# electric_imp_breakout.net
KiCad netlist of a schematic drawn in EAGLE
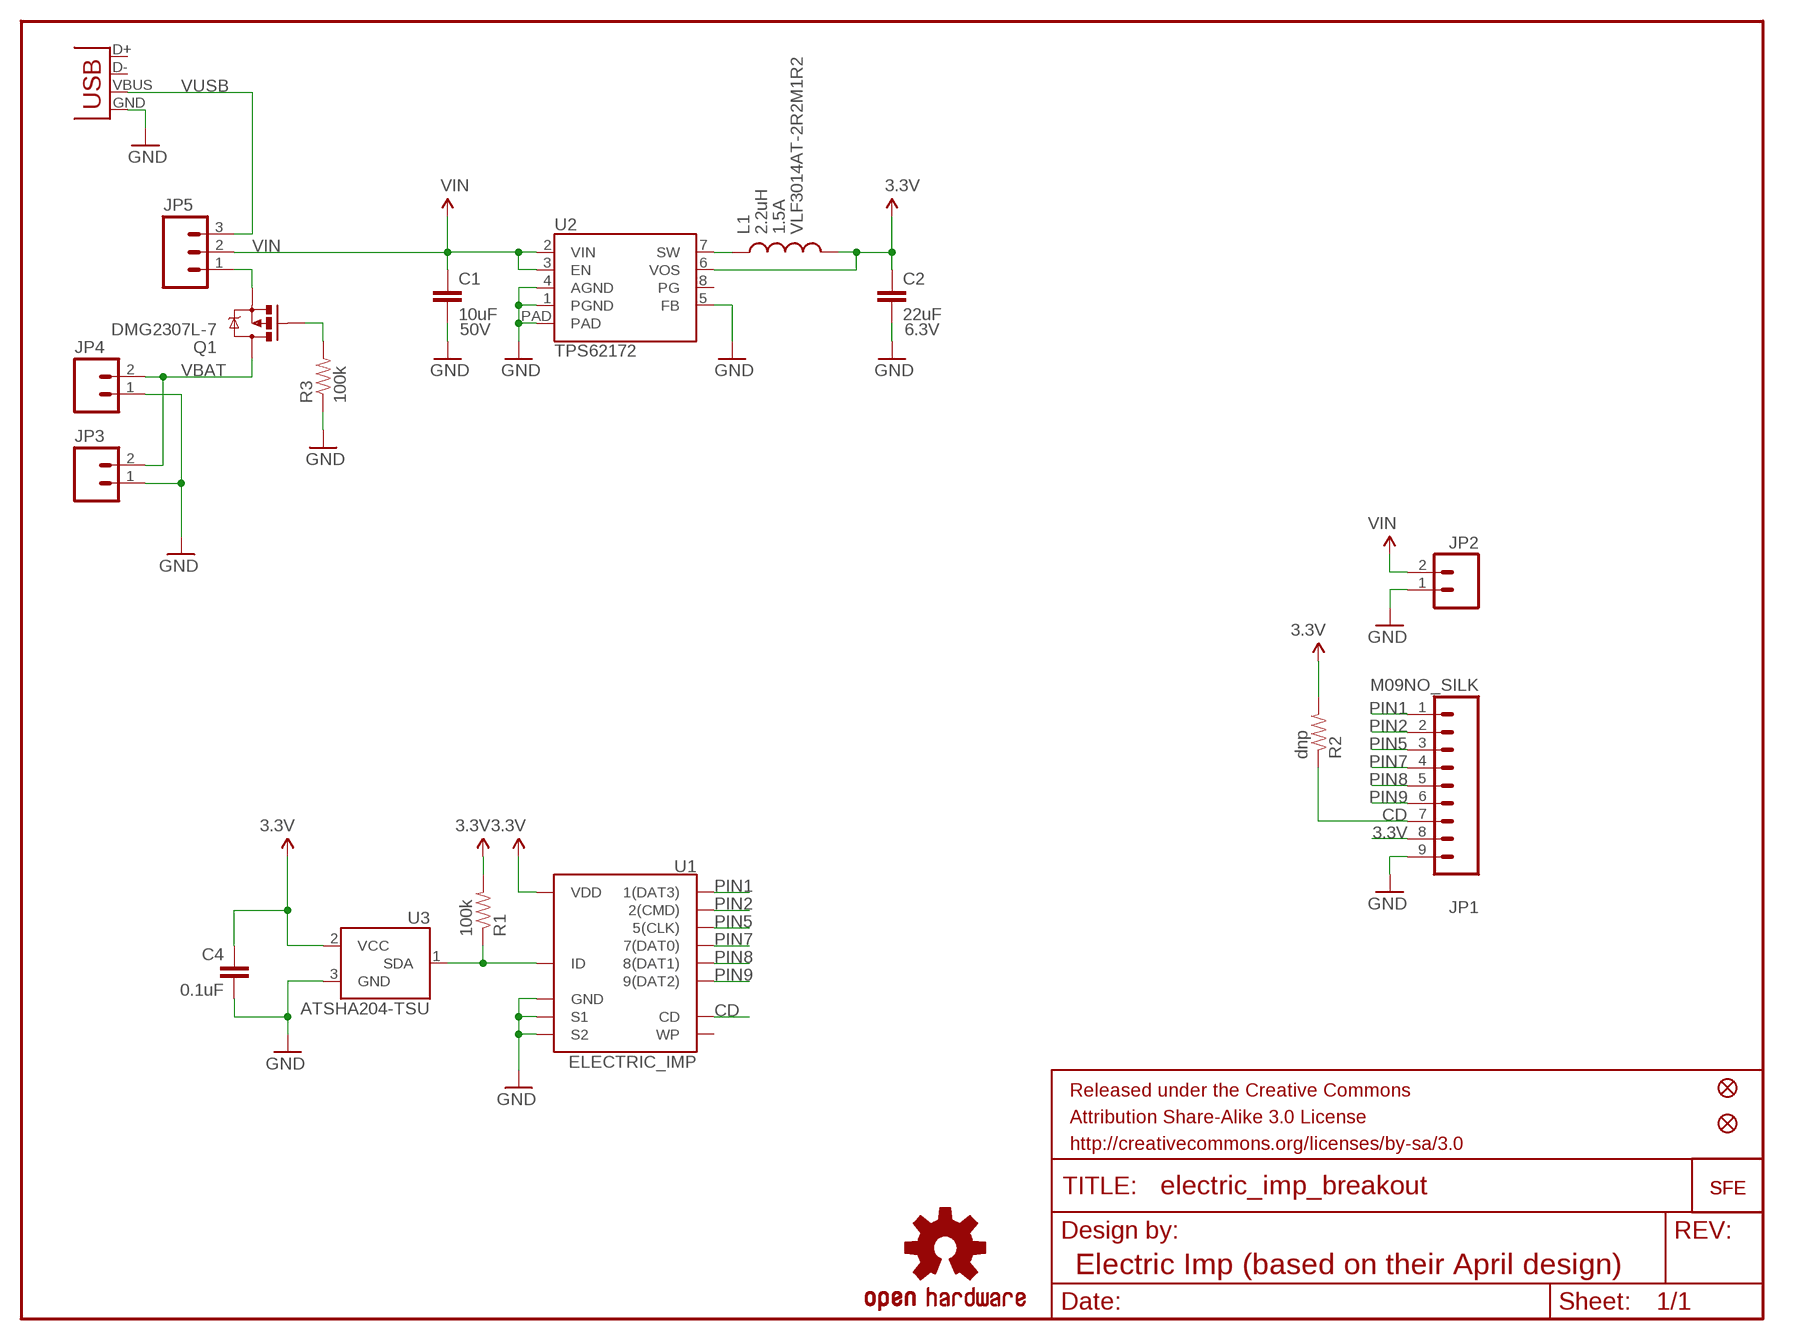
[diagram p0: schematic, sheet 1]

(export (version "E")
  (design (tool "Eeschema 10.0.6"))
  (components
    (comp (ref "C1")
      (value "10uF")
      (footprint "eagle-import:1210")
      (libsource (lib "eagle-import") (part "CAP1210"))
    )
    (comp (ref "C2")
      (value "22uF")
      (footprint "eagle-import:0805")
      (libsource (lib "eagle-import") (part "CAP0805"))
    )
    (comp (ref "C4")
      (value "0.1uF")
      (footprint "eagle-import:0402-CAP")
      (libsource (lib "eagle-import") (part "CAP0402-CAP"))
    )
    (comp (ref "JP1")
      (value "M09NO_SILK")
      (footprint "eagle-import:1X09_NO_SILK")
      (libsource (lib "eagle-import") (part "M09NO_SILK"))
    )
    (comp (ref "JP2")
      (value "M021X02_NO_SILK")
      (footprint "eagle-import:1X02_NO_SILK")
      (libsource (lib "eagle-import") (part "M021X02_NO_SILK"))
    )
    (comp (ref "JP3")
      (value "M02SMD")
      (footprint "eagle-import:1X02_SMD")
      (libsource (lib "eagle-import") (part "M02SMD"))
    )
    (comp (ref "JP4")
      (value "M02-JST-2-PTH-NO_SILK")
      (footprint "eagle-import:JST-2-PTH-NS")
      (libsource (lib "eagle-import") (part "M02-JST-2-PTH-NO_SILK"))
    )
    (comp (ref "JP5")
      (value "M031X03_NO_SILK")
      (footprint "eagle-import:1X03_NO_SILK")
      (libsource (lib "eagle-import") (part "M031X03_NO_SILK"))
    )
    (comp (ref "JP6")
      (value "LOGO-SFESK")
      (footprint "eagle-import:SFE-LOGO-FLAME")
      (libsource (lib "eagle-import") (part "LOGO-SFESK"))
    )
    (comp (ref "JP7")
      (value "LOGO-SFENEW")
      (footprint "eagle-import:SFE-NEW-WEBLOGO")
      (libsource (lib "eagle-import") (part "LOGO-SFENEW"))
    )
    (comp (ref "JP8")
      (value "FIDUCIALUFIDUCIAL")
      (footprint "eagle-import:MICRO-FIDUCIAL")
      (libsource (lib "eagle-import") (part "FIDUCIALUFIDUCIAL"))
    )
    (comp (ref "JP9")
      (value "FIDUCIALUFIDUCIAL")
      (footprint "eagle-import:MICRO-FIDUCIAL")
      (libsource (lib "eagle-import") (part "FIDUCIALUFIDUCIAL"))
    )
    (comp (ref "L1")
      (value "2.2uH")
      (footprint "eagle-import:VLF4012A")
      (libsource (lib "eagle-import") (part "INDUCTORVLF4012A"))
    )
    (comp (ref "Q1")
      (value "DMG2307L-7")
      (footprint "eagle-import:SOT23-3")
      (libsource (lib "eagle-import") (part "MOSFET-PCHANNELSMD"))
    )
    (comp (ref "R1")
      (value "100k")
      (footprint "eagle-import:0402-RES")
      (libsource (lib "eagle-import") (part "RESISTOR0402-RES"))
    )
    (comp (ref "R2")
      (value "dnp")
      (footprint "eagle-import:0402-RES")
      (libsource (lib "eagle-import") (part "RESISTOR0402-RES"))
    )
    (comp (ref "R3")
      (value "100k")
      (footprint "eagle-import:0402-RES")
      (libsource (lib "eagle-import") (part "RESISTOR0402-RES"))
    )
    (comp (ref "U$5")
      (value "OSHW-LOGOS")
      (footprint "eagle-import:OSHW-LOGO-S")
      (libsource (lib "eagle-import") (part "OSHW-LOGOS"))
    )
    (comp (ref "U1")
      (value "ELECTRIC_IMP")
      (footprint "eagle-import:SD_MMC_SOCKET")
      (libsource (lib "eagle-import") (part "ELECTRIC_IMP"))
    )
    (comp (ref "U2")
      (value "TPS62172")
      (footprint "eagle-import:WSON-8-PAD")
      (libsource (lib "eagle-import") (part "TPS62172"))
    )
    (comp (ref "U3")
      (value "ATSHA204-TSU")
      (footprint "eagle-import:SOT23-3")
      (libsource (lib "eagle-import") (part "ATSHA204-TSU"))
    )
    (comp (ref "X1")
      (value "USBSMD")
      (footprint "eagle-import:USB-MINIB")
      (libsource (lib "eagle-import") (part "USBSMD"))
    )
  )
  (nets
    (net (code "1") (name "/CD") (class "Default")
      (node (ref "JP1") (pin "7") (pinfunction "7_7") (pintype "passive"))
      (node (ref "R2") (pin "1") (pinfunction "1_1") (pintype "passive"))
      (node (ref "U1") (pin "CD") (pinfunction "CD_CD") (pintype "bidirectional"))
    )
    (net (code "2") (name "/PIN1") (class "Default")
      (node (ref "JP1") (pin "1") (pinfunction "1_1") (pintype "passive"))
      (node (ref "U1") (pin "1") (pinfunction "1(DAT3)_1") (pintype "bidirectional"))
    )
    (net (code "3") (name "/PIN2") (class "Default")
      (node (ref "JP1") (pin "2") (pinfunction "2_2") (pintype "passive"))
      (node (ref "U1") (pin "2") (pinfunction "2(CMD)_2") (pintype "bidirectional"))
    )
    (net (code "4") (name "/PIN5") (class "Default")
      (node (ref "JP1") (pin "3") (pinfunction "3_3") (pintype "passive"))
      (node (ref "U1") (pin "5") (pinfunction "5(CLK)_5") (pintype "bidirectional"))
    )
    (net (code "5") (name "/PIN7") (class "Default")
      (node (ref "JP1") (pin "4") (pinfunction "4_4") (pintype "passive"))
      (node (ref "U1") (pin "7") (pinfunction "7(DAT0)_7") (pintype "bidirectional"))
    )
    (net (code "6") (name "/PIN8") (class "Default")
      (node (ref "JP1") (pin "5") (pinfunction "5_5") (pintype "passive"))
      (node (ref "U1") (pin "8") (pinfunction "8(DAT1)_8") (pintype "bidirectional"))
    )
    (net (code "7") (name "/PIN9") (class "Default")
      (node (ref "JP1") (pin "6") (pinfunction "6_6") (pintype "passive"))
      (node (ref "U1") (pin "9") (pinfunction "9(DAT2)_9") (pintype "bidirectional"))
    )
    (net (code "8") (name "/VBAT") (class "Default")
      (node (ref "JP3") (pin "2") (pinfunction "2_2") (pintype "passive"))
      (node (ref "JP4") (pin "2") (pinfunction "2_2") (pintype "passive"))
      (node (ref "Q1") (pin "3") (pinfunction "D_3") (pintype "passive"))
    )
    (net (code "9") (name "/VUSB") (class "Default")
      (node (ref "JP5") (pin "3") (pinfunction "3_3") (pintype "passive"))
      (node (ref "X1") (pin "VBUS") (pinfunction "VBUS_VBUS") (pintype "bidirectional"))
    )
    (net (code "10") (name "3.3V") (class "Default")
      (node (ref "C2") (pin "1") (pinfunction "1_1") (pintype "passive"))
      (node (ref "C4") (pin "1") (pinfunction "1_1") (pintype "passive"))
      (node (ref "JP1") (pin "8") (pinfunction "8_8") (pintype "passive"))
      (node (ref "L1") (pin "P$2") (pinfunction "2_P$2") (pintype "passive"))
      (node (ref "R1") (pin "2") (pinfunction "2_2") (pintype "passive"))
      (node (ref "R2") (pin "2") (pinfunction "2_2") (pintype "passive"))
      (node (ref "U1") (pin "4") (pinfunction "VDD_4") (pintype "bidirectional"))
      (node (ref "U2") (pin "6") (pinfunction "VOS_6") (pintype "bidirectional"))
      (node (ref "U3") (pin "2") (pinfunction "VCC_2") (pintype "bidirectional"))
    )
    (net (code "11") (name "GND") (class "Default")
      (node (ref "C1") (pin "2") (pinfunction "2_2") (pintype "passive"))
      (node (ref "C2") (pin "2") (pinfunction "2_2") (pintype "passive"))
      (node (ref "C4") (pin "2") (pinfunction "2_2") (pintype "passive"))
      (node (ref "JP1") (pin "9") (pinfunction "9_9") (pintype "passive"))
      (node (ref "JP2") (pin "1") (pinfunction "1_1") (pintype "passive"))
      (node (ref "JP3") (pin "1") (pinfunction "1_1") (pintype "passive"))
      (node (ref "JP4") (pin "1") (pinfunction "1_1") (pintype "passive"))
      (node (ref "R3") (pin "1") (pinfunction "1_1") (pintype "passive"))
      (node (ref "U1") (pin "3") (pinfunction "GND_3") (pintype "bidirectional"))
      (node (ref "U1") (pin "S1") (pinfunction "S1_S1") (pintype "bidirectional"))
      (node (ref "U1") (pin "S2") (pinfunction "S2_S2") (pintype "bidirectional"))
      (node (ref "U2") (pin "1") (pinfunction "PGND_1") (pintype "bidirectional"))
      (node (ref "U2") (pin "4") (pinfunction "AGND_4") (pintype "bidirectional"))
      (node (ref "U2") (pin "5") (pinfunction "FB_5") (pintype "bidirectional"))
      (node (ref "U2") (pin "PAD") (pinfunction "PAD_PAD") (pintype "bidirectional"))
      (node (ref "U3") (pin "3") (pinfunction "GND_3") (pintype "bidirectional"))
      (node (ref "X1") (pin "GND") (pinfunction "GND_GND") (pintype "bidirectional"))
    )
    (net (code "12") (name "Net-(L1-1)") (class "Default")
      (node (ref "L1") (pin "P$1") (pinfunction "1_P$1") (pintype "passive"))
      (node (ref "U2") (pin "7") (pinfunction "SW_7") (pintype "bidirectional"))
    )
    (net (code "13") (name "Net-(Q1-G)") (class "Default")
      (node (ref "Q1") (pin "1") (pinfunction "G_1") (pintype "passive"))
      (node (ref "R3") (pin "2") (pinfunction "2_2") (pintype "passive"))
    )
    (net (code "14") (name "Net-(Q1-S)") (class "Default")
      (node (ref "JP5") (pin "1") (pinfunction "1_1") (pintype "passive"))
      (node (ref "Q1") (pin "2") (pinfunction "S_2") (pintype "passive"))
    )
    (net (code "15") (name "Net-(U1-ID)") (class "Default")
      (node (ref "R1") (pin "1") (pinfunction "1_1") (pintype "passive"))
      (node (ref "U1") (pin "6") (pinfunction "ID_6") (pintype "bidirectional"))
      (node (ref "U3") (pin "1") (pinfunction "SDA_1") (pintype "bidirectional"))
    )
    (net (code "16") (name "VIN") (class "Default")
      (node (ref "C1") (pin "1") (pinfunction "1_1") (pintype "passive"))
      (node (ref "JP2") (pin "2") (pinfunction "2_2") (pintype "passive"))
      (node (ref "JP5") (pin "2") (pinfunction "2_2") (pintype "passive"))
      (node (ref "U2") (pin "2") (pinfunction "VIN_2") (pintype "bidirectional"))
      (node (ref "U2") (pin "3") (pinfunction "EN_3") (pintype "bidirectional"))
    )
    (net (code "17") (name "unconnected-(U1-PadWP)") (class "Default")
      (node (ref "U1") (pin "WP") (pinfunction "WP_WP") (pintype "bidirectional"))
    )
    (net (code "18") (name "unconnected-(U2-PG-Pad8)") (class "Default")
      (node (ref "U2") (pin "8") (pinfunction "PG_8") (pintype "bidirectional"))
    )
    (net (code "19") (name "unconnected-(X1-PadD+)") (class "Default")
      (node (ref "X1") (pin "D+") (pinfunction "D+_D+") (pintype "bidirectional"))
    )
    (net (code "20") (name "unconnected-(X1-PadD-)") (class "Default")
      (node (ref "X1") (pin "D-") (pinfunction "D-_D-") (pintype "bidirectional"))
    )
  )
)
